# Tempidity_Luxe.net
KiCad netlist of a schematic drawn in EAGLE
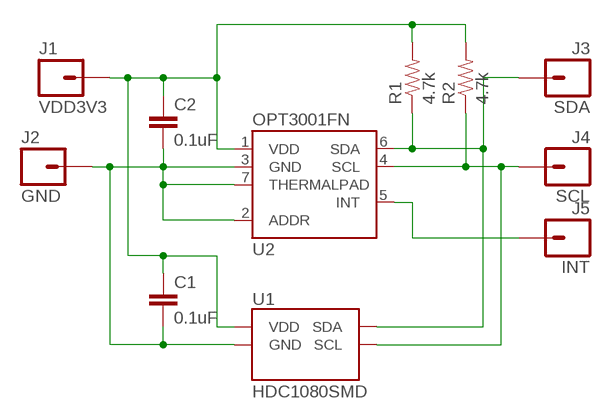
[diagram p0: schematic, sheet 1]

(export (version "E")
  (design (tool "Eeschema 10.0.6"))
  (components
    (comp (ref "C1")
      (value "0.1uF")
      (footprint "eagle-import:0805")
      (libsource (lib "eagle-import") (part "CAP0805"))
    )
    (comp (ref "C2")
      (value "0.1uF")
      (footprint "eagle-import:0805")
      (libsource (lib "eagle-import") (part "CAP0805"))
    )
    (comp (ref "J1")
      (value "VDD3V3")
      (footprint "eagle-import:1X01_NO_SILK")
      (libsource (lib "eagle-import") (part "M01PTH_NO_SILK_YES_STOP"))
    )
    (comp (ref "J2")
      (value "GND")
      (footprint "eagle-import:1X01_NO_SILK")
      (libsource (lib "eagle-import") (part "M01PTH_NO_SILK_YES_STOP"))
    )
    (comp (ref "J3")
      (value "SDA")
      (footprint "eagle-import:1X01_NO_SILK")
      (libsource (lib "eagle-import") (part "M01PTH_NO_SILK_YES_STOP"))
    )
    (comp (ref "J4")
      (value "SCL")
      (footprint "eagle-import:1X01_NO_SILK")
      (libsource (lib "eagle-import") (part "M01PTH_NO_SILK_YES_STOP"))
    )
    (comp (ref "J5")
      (value "INT")
      (footprint "eagle-import:1X01_NO_SILK")
      (libsource (lib "eagle-import") (part "M01PTH_NO_SILK_YES_STOP"))
    )
    (comp (ref "R1")
      (value "4.7k")
      (footprint "eagle-import:0805")
      (libsource (lib "eagle-import") (part "RESISTOR0805-RES"))
    )
    (comp (ref "R2")
      (value "4.7k")
      (footprint "eagle-import:0805")
      (libsource (lib "eagle-import") (part "RESISTOR0805-RES"))
    )
    (comp (ref "U1")
      (value "HDC1080SMD")
      (footprint "eagle-import:TI-PWSON6-DMB")
      (libsource (lib "eagle-import") (part "HDC1080SMD"))
    )
    (comp (ref "U2")
      (value "OPT3001FN")
      (footprint "eagle-import:TI-USON6-GND-PAD")
      (libsource (lib "eagle-import") (part "OPT3001FN"))
    )
  )
  (nets
    (net (code "1") (name "Net-(U2-ADDR)") (class "Default")
      (node (ref "C1") (pin "2") (pinfunction "2_2") (pintype "passive"))
      (node (ref "C2") (pin "2") (pinfunction "2_2") (pintype "passive"))
      (node (ref "J2") (pin "1") (pinfunction "1_1") (pintype "passive"))
      (node (ref "U1") (pin "GND") (pinfunction "GND_GND") (pintype "power_in"))
      (node (ref "U2") (pin "2") (pinfunction "ADDR_2") (pintype "input"))
      (node (ref "U2") (pin "3") (pinfunction "GND_3") (pintype "power_in"))
      (node (ref "U2") (pin "7") (pinfunction "THERMALPAD_7") (pintype "power_in"))
    )
    (net (code "2") (name "Net-(U2-INT)") (class "Default")
      (node (ref "J5") (pin "1") (pinfunction "1_1") (pintype "passive"))
      (node (ref "U2") (pin "5") (pinfunction "INT_5") (pintype "output"))
    )
    (net (code "3") (name "Net-(U2-SCL)") (class "Default")
      (node (ref "J4") (pin "1") (pinfunction "1_1") (pintype "passive"))
      (node (ref "R2") (pin "1") (pinfunction "1_1") (pintype "passive"))
      (node (ref "U1") (pin "SCL") (pinfunction "SCL_SCL") (pintype "input"))
      (node (ref "U2") (pin "4") (pinfunction "SCL_4") (pintype "input"))
    )
    (net (code "4") (name "Net-(U2-SDA)") (class "Default")
      (node (ref "J3") (pin "1") (pinfunction "1_1") (pintype "passive"))
      (node (ref "R1") (pin "1") (pinfunction "1_1") (pintype "passive"))
      (node (ref "U1") (pin "SDA") (pinfunction "SDA_SDA") (pintype "bidirectional"))
      (node (ref "U2") (pin "6") (pinfunction "SDA_6") (pintype "bidirectional"))
    )
    (net (code "5") (name "Net-(U2-VDD)") (class "Default")
      (node (ref "C1") (pin "1") (pinfunction "1_1") (pintype "passive"))
      (node (ref "C2") (pin "1") (pinfunction "1_1") (pintype "passive"))
      (node (ref "J1") (pin "1") (pinfunction "1_1") (pintype "passive"))
      (node (ref "R1") (pin "2") (pinfunction "2_2") (pintype "passive"))
      (node (ref "R2") (pin "2") (pinfunction "2_2") (pintype "passive"))
      (node (ref "U1") (pin "VDD") (pinfunction "VDD_VDD") (pintype "power_in"))
      (node (ref "U2") (pin "1") (pinfunction "VDD_1") (pintype "power_in"))
    )
  )
)
